# stm32.net
KiCad netlist of a schematic drawn in Altium Designer
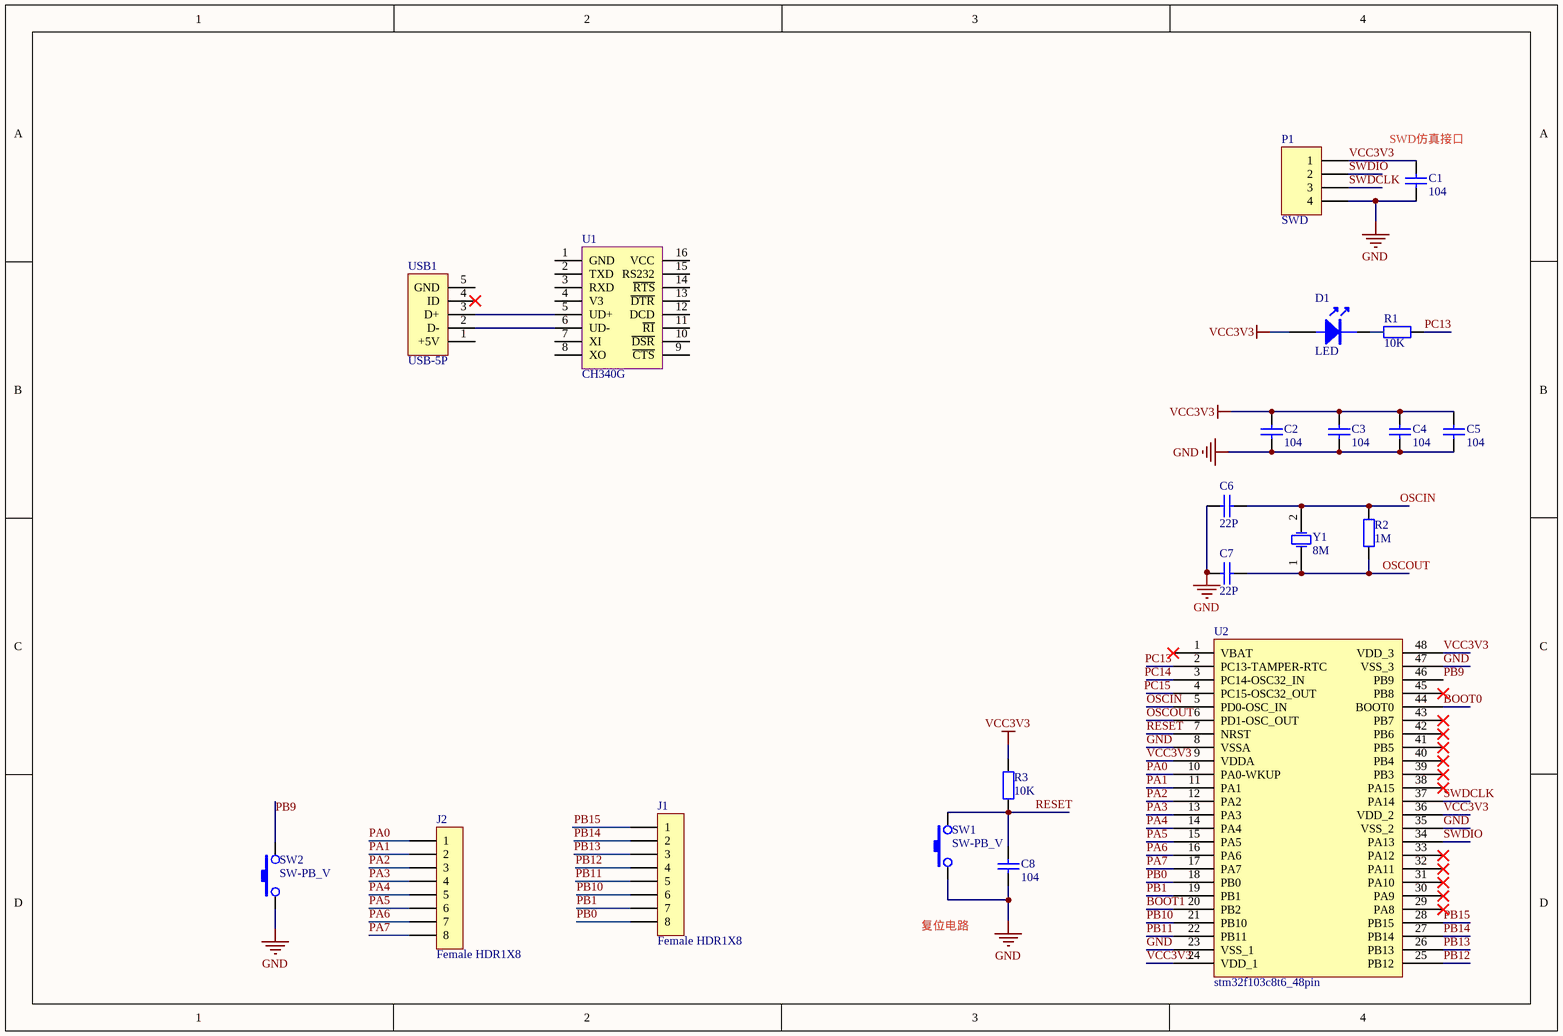
[diagram p0: stm32最小系统.SchDoc]

(export (version "E")
  (design (tool "Eeschema 10.0.6"))
  (components
    (comp (ref "C1")
      (value "104")
      (footprint "0805R")
      (fields (field (name "PUBLISHER") "Altium Limited"))
      (libsource (lib "stm32原理图库") (part "Cap"))
    )
    (comp (ref "C2")
      (value "104")
      (footprint "0805R")
      (fields (field (name "PUBLISHER") "Altium Limited"))
      (libsource (lib "stm32原理图库") (part "Cap"))
    )
    (comp (ref "C3")
      (value "104")
      (fields (field (name "PUBLISHER") "Altium Limited"))
      (libsource (lib "stm32原理图库") (part "Cap"))
    )
    (comp (ref "C4")
      (value "104")
      (fields (field (name "PUBLISHER") "Altium Limited"))
      (libsource (lib "stm32原理图库") (part "Cap"))
    )
    (comp (ref "C5")
      (value "104")
      (fields (field (name "PUBLISHER") "Altium Limited"))
      (libsource (lib "stm32原理图库") (part "Cap"))
    )
    (comp (ref "C6")
      (value "22P")
      (description "Capacitor")
      (fields (field (name "PUBLISHER") "Altium Limited"))
      (libsource (lib "STM32F103C8T6") (part "Cap"))
    )
    (comp (ref "C7")
      (value "22P")
      (description "Capacitor")
      (fields (field (name "PUBLISHER") "Altium Limited"))
      (libsource (lib "STM32F103C8T6") (part "Cap"))
    )
    (comp (ref "C8")
      (value "104")
      (footprint "0805C")
      (fields (field (name "PUBLISHER") "Altium Limited"))
      (libsource (lib "stm32原理图库") (part "Cap"))
    )
    (comp (ref "D1") (value "LED") (footprint "LED 0805G") (libsource (lib "stm32原理图库") (part "LED")))
    (comp (ref "J1")
      (value "Female HDR1X8")
      (footprint "Fe-HDR1X8/2.54-S")
      (libsource (lib "排母") (part "Female HDR1X8"))
    )
    (comp (ref "J2")
      (value "Female HDR1X8")
      (footprint "Fe-HDR1X8/2.54-S")
      (libsource (lib "排母") (part "Female HDR1X8"))
    )
    (comp (ref "P1")
      (value "SWD")
      (footprint "HDR-1X4_H")
      (description "Header, 4-Pin")
      (fields (field (name "PUBLISHER") "Altium Limited"))
      (libsource (lib "stm32原理图库") (part "Header 4"))
    )
    (comp (ref "R1")
      (value "10K")
      (footprint "C0805")
      (fields (field (name "PUBLISHER") "Altium Limited"))
      (libsource (lib "stm32原理图库") (part "Res2"))
    )
    (comp (ref "R2")
      (value "1M")
      (footprint "C0805")
      (description "Resistor")
      (fields (field (name "PUBLISHER") "Altium Limited"))
      (libsource (lib "STM32F103C8T6") (part "Res2"))
    )
    (comp (ref "R3")
      (value "10K")
      (footprint "C0805")
      (fields (field (name "PUBLISHER") "Altium Limited"))
      (libsource (lib "") (part "Res2_1"))
    )
    (comp (ref "SW1")
      (value "SW-PB_V")
      (footprint "TSW SMD-3*6*2.5")
      (libsource (lib "stm32原理图库") (part "SW-PB_V"))
    )
    (comp (ref "SW2")
      (value "SW-PB_V")
      (footprint "TSW SMD-3*6*2.5")
      (libsource (lib "stm32原理图库") (part "SW-PB_V"))
    )
    (comp (ref "U1") (value "CH340G") (libsource (lib "通讯系列IC") (part "CH340G")))
    (comp (ref "U2")
      (value "stm32f103c8t6_48pin")
      (footprint "TQFP48 7x7_L")
      (libsource (lib "STM32_Schlib") (part "stm32f103c8t6_48pin"))
    )
    (comp (ref "USB1")
      (value "USB-5P")
      (footprint "USB-MICRO_E")
      (description "微型USB母座")
      (fields (field (name "版权归属") "源创客"))
      (libsource (lib "4.1   - 接口类") (part "USB-5P"))
    )
    (comp (ref "Y1")
      (value "8M")
      (footprint "XTAL-49S DIP")
      (description "Crystal Oscillator")
      (fields (field (name "PUBLISHER") "Altium Limited"))
      (libsource (lib "STM32F103C8T6") (part "XTAL"))
    )
  )
  (nets
    (net (code "1") (name "/BOOT0") (class "Default")
      (node (ref "U2") (pin "44") (pinfunction "BOOT0_44") (pintype "passive"))
    )
    (net (code "2") (name "/BOOT1") (class "Default")
      (node (ref "U2") (pin "20") (pinfunction "PB2_20") (pintype "passive"))
    )
    (net (code "3") (name "/OSCIN") (class "Default")
      (node (ref "C6") (pin "1") (pinfunction "1_1") (pintype "passive"))
      (node (ref "R2") (pin "2") (pinfunction "2_2") (pintype "passive"))
      (node (ref "U2") (pin "5") (pinfunction "PD0-OSC_IN_5") (pintype "passive"))
      (node (ref "Y1") (pin "2") (pinfunction "OSC2_2") (pintype "passive"))
    )
    (net (code "4") (name "/OSCOUT") (class "Default")
      (node (ref "C7") (pin "1") (pinfunction "1_1") (pintype "passive"))
      (node (ref "R2") (pin "1") (pinfunction "1_1") (pintype "passive"))
      (node (ref "U2") (pin "6") (pinfunction "PD1-OSC_OUT_6") (pintype "passive"))
      (node (ref "Y1") (pin "1") (pinfunction "OSC1_1") (pintype "passive"))
    )
    (net (code "5") (name "/PA0") (class "Default")
      (node (ref "J2") (pin "1") (pinfunction "1_1") (pintype "passive"))
      (node (ref "U2") (pin "10") (pinfunction "PA0-WKUP_10") (pintype "passive"))
    )
    (net (code "6") (name "/PA1") (class "Default")
      (node (ref "J2") (pin "2") (pinfunction "2_2") (pintype "passive"))
      (node (ref "U2") (pin "11") (pinfunction "PA1_11") (pintype "passive"))
    )
    (net (code "7") (name "/PA2") (class "Default")
      (node (ref "J2") (pin "3") (pinfunction "3_3") (pintype "passive"))
      (node (ref "U2") (pin "12") (pinfunction "PA2_12") (pintype "passive"))
    )
    (net (code "8") (name "/PA3") (class "Default")
      (node (ref "J2") (pin "4") (pinfunction "4_4") (pintype "passive"))
      (node (ref "U2") (pin "13") (pinfunction "PA3_13") (pintype "passive"))
    )
    (net (code "9") (name "/PA4") (class "Default")
      (node (ref "J2") (pin "5") (pinfunction "5_5") (pintype "passive"))
      (node (ref "U2") (pin "14") (pinfunction "PA4_14") (pintype "passive"))
    )
    (net (code "10") (name "/PA5") (class "Default")
      (node (ref "J2") (pin "6") (pinfunction "6_6") (pintype "passive"))
      (node (ref "U2") (pin "15") (pinfunction "PA5_15") (pintype "passive"))
    )
    (net (code "11") (name "/PA6") (class "Default")
      (node (ref "J2") (pin "7") (pinfunction "7_7") (pintype "passive"))
      (node (ref "U2") (pin "16") (pinfunction "PA6_16") (pintype "passive"))
    )
    (net (code "12") (name "/PA7") (class "Default")
      (node (ref "J2") (pin "8") (pinfunction "8_8") (pintype "passive"))
      (node (ref "U2") (pin "17") (pinfunction "PA7_17") (pintype "passive"))
    )
    (net (code "13") (name "/PB0") (class "Default")
      (node (ref "J1") (pin "8") (pinfunction "8_8") (pintype "passive"))
      (node (ref "U2") (pin "18") (pinfunction "PB0_18") (pintype "passive"))
    )
    (net (code "14") (name "/PB1") (class "Default")
      (node (ref "J1") (pin "7") (pinfunction "7_7") (pintype "passive"))
      (node (ref "U2") (pin "19") (pinfunction "PB1_19") (pintype "passive"))
    )
    (net (code "15") (name "/PB9") (class "Default")
      (node (ref "SW2") (pin "2") (pinfunction "2_2") (pintype "passive"))
      (node (ref "U2") (pin "46") (pinfunction "PB9_46") (pintype "passive"))
    )
    (net (code "16") (name "/PB10") (class "Default")
      (node (ref "J1") (pin "6") (pinfunction "6_6") (pintype "passive"))
      (node (ref "U2") (pin "21") (pinfunction "PB10_21") (pintype "passive"))
    )
    (net (code "17") (name "/PB11") (class "Default")
      (node (ref "J1") (pin "5") (pinfunction "5_5") (pintype "passive"))
      (node (ref "U2") (pin "22") (pinfunction "PB11_22") (pintype "passive"))
    )
    (net (code "18") (name "/PB12") (class "Default")
      (node (ref "J1") (pin "4") (pinfunction "4_4") (pintype "passive"))
      (node (ref "U2") (pin "25") (pinfunction "PB12_25") (pintype "passive"))
    )
    (net (code "19") (name "/PB13") (class "Default")
      (node (ref "J1") (pin "3") (pinfunction "3_3") (pintype "passive"))
      (node (ref "U2") (pin "26") (pinfunction "PB13_26") (pintype "passive"))
    )
    (net (code "20") (name "/PB14") (class "Default")
      (node (ref "J1") (pin "2") (pinfunction "2_2") (pintype "passive"))
      (node (ref "U2") (pin "27") (pinfunction "PB14_27") (pintype "passive"))
    )
    (net (code "21") (name "/PB15") (class "Default")
      (node (ref "J1") (pin "1") (pinfunction "1_1") (pintype "passive"))
      (node (ref "U2") (pin "28") (pinfunction "PB15_28") (pintype "passive"))
    )
    (net (code "22") (name "/PC13") (class "Default")
      (node (ref "R1") (pin "2") (pinfunction "2_2") (pintype "passive"))
      (node (ref "U2") (pin "2") (pinfunction "PC13-TAMPER-RTC_2") (pintype "passive"))
    )
    (net (code "23") (name "/PC14") (class "Default")
      (node (ref "U2") (pin "3") (pinfunction "PC14-OSC32_IN_3") (pintype "passive"))
    )
    (net (code "24") (name "/PC15") (class "Default")
      (node (ref "U2") (pin "4") (pinfunction "PC15-OSC32_OUT_4") (pintype "passive"))
    )
    (net (code "25") (name "/RESET") (class "Default")
      (node (ref "C8") (pin "2") (pinfunction "2_2") (pintype "passive"))
      (node (ref "R3") (pin "1") (pinfunction "1_1") (pintype "passive"))
      (node (ref "SW1") (pin "2") (pinfunction "2_2") (pintype "passive"))
      (node (ref "U2") (pin "7") (pinfunction "NRST_7") (pintype "passive"))
    )
    (net (code "26") (name "/SWDCLK") (class "Default")
      (node (ref "P1") (pin "3") (pinfunction "3_3") (pintype "passive"))
      (node (ref "U2") (pin "37") (pinfunction "PA14_37") (pintype "passive"))
    )
    (net (code "27") (name "/SWDIO") (class "Default")
      (node (ref "P1") (pin "2") (pinfunction "2_2") (pintype "passive"))
      (node (ref "U2") (pin "34") (pinfunction "PA13_34") (pintype "passive"))
    )
    (net (code "28") (name "GND") (class "Default")
      (node (ref "C1") (pin "1") (pinfunction "1_1") (pintype "passive"))
      (node (ref "C2") (pin "1") (pinfunction "1_1") (pintype "passive"))
      (node (ref "C3") (pin "1") (pinfunction "1_1") (pintype "passive"))
      (node (ref "C4") (pin "1") (pinfunction "1_1") (pintype "passive"))
      (node (ref "C5") (pin "1") (pinfunction "1_1") (pintype "passive"))
      (node (ref "C6") (pin "2") (pinfunction "2_2") (pintype "passive"))
      (node (ref "C7") (pin "2") (pinfunction "2_2") (pintype "passive"))
      (node (ref "C8") (pin "1") (pinfunction "1_1") (pintype "passive"))
      (node (ref "P1") (pin "4") (pinfunction "4_4") (pintype "passive"))
      (node (ref "SW1") (pin "1") (pinfunction "1_1") (pintype "passive"))
      (node (ref "SW2") (pin "1") (pinfunction "1_1") (pintype "passive"))
      (node (ref "U2") (pin "23") (pinfunction "VSS_1_23") (pintype "passive"))
      (node (ref "U2") (pin "35") (pinfunction "VSS_2_35") (pintype "passive"))
      (node (ref "U2") (pin "47") (pinfunction "VSS_3_47") (pintype "passive"))
      (node (ref "U2") (pin "8") (pinfunction "VSSA_8") (pintype "passive"))
    )
    (net (code "29") (name "Net-(D1-Pad2)") (class "Default")
      (node (ref "D1") (pin "2") (pinfunction "2_2") (pintype "passive"))
      (node (ref "R1") (pin "1") (pinfunction "1_1") (pintype "passive"))
    )
    (net (code "30") (name "Net-(U1-UD+)") (class "Default")
      (node (ref "U1") (pin "5") (pinfunction "UD+_5") (pintype "passive"))
      (node (ref "USB1") (pin "3") (pinfunction "D+_3") (pintype "passive"))
    )
    (net (code "31") (name "Net-(U1-UD-)") (class "Default")
      (node (ref "U1") (pin "6") (pinfunction "UD-_6") (pintype "passive"))
      (node (ref "USB1") (pin "2") (pinfunction "D-_2") (pintype "passive"))
    )
    (net (code "32") (name "VCC3V3") (class "Default")
      (node (ref "C1") (pin "2") (pinfunction "2_2") (pintype "passive"))
      (node (ref "C2") (pin "2") (pinfunction "2_2") (pintype "passive"))
      (node (ref "C3") (pin "2") (pinfunction "2_2") (pintype "passive"))
      (node (ref "C4") (pin "2") (pinfunction "2_2") (pintype "passive"))
      (node (ref "C5") (pin "2") (pinfunction "2_2") (pintype "passive"))
      (node (ref "D1") (pin "1") (pinfunction "1_1") (pintype "passive"))
      (node (ref "P1") (pin "1") (pinfunction "1_1") (pintype "passive"))
      (node (ref "R3") (pin "2") (pinfunction "2_2") (pintype "passive"))
      (node (ref "U2") (pin "24") (pinfunction "VDD_1_24") (pintype "passive"))
      (node (ref "U2") (pin "36") (pinfunction "VDD_2_36") (pintype "passive"))
      (node (ref "U2") (pin "48") (pinfunction "VDD_3_48") (pintype "passive"))
      (node (ref "U2") (pin "9") (pinfunction "VDDA_9") (pintype "passive"))
    )
    (net (code "33") (name "unconnected-(U1-DCD-Pad12)") (class "Default")
      (node (ref "U1") (pin "12") (pinfunction "DCD_12") (pintype "passive"))
    )
    (net (code "34") (name "unconnected-(U1-GND-Pad1)") (class "Default")
      (node (ref "U1") (pin "1") (pinfunction "GND_1") (pintype "passive"))
    )
    (net (code "35") (name "unconnected-(U1-RS232-Pad15)") (class "Default")
      (node (ref "U1") (pin "15") (pinfunction "RS232_15") (pintype "passive"))
    )
    (net (code "36") (name "unconnected-(U1-RXD-Pad3)") (class "Default")
      (node (ref "U1") (pin "3") (pinfunction "RXD_3") (pintype "passive"))
    )
    (net (code "37") (name "unconnected-(U1-TXD-Pad2)") (class "Default")
      (node (ref "U1") (pin "2") (pinfunction "TXD_2") (pintype "passive"))
    )
    (net (code "38") (name "unconnected-(U1-V3-Pad4)") (class "Default")
      (node (ref "U1") (pin "4") (pinfunction "V3_4") (pintype "passive"))
    )
    (net (code "39") (name "unconnected-(U1-VCC-Pad16)") (class "Default")
      (node (ref "U1") (pin "16") (pinfunction "VCC_16") (pintype "passive"))
    )
    (net (code "40") (name "unconnected-(U1-XI-Pad7)") (class "Default")
      (node (ref "U1") (pin "7") (pinfunction "XI_7") (pintype "passive"))
    )
    (net (code "41") (name "unconnected-(U1-XO-Pad8)") (class "Default")
      (node (ref "U1") (pin "8") (pinfunction "XO_8") (pintype "passive"))
    )
    (net (code "42") (name "unconnected-(U1-~{CTS}-Pad9)") (class "Default")
      (node (ref "U1") (pin "9") (pinfunction "~{CTS}_9") (pintype "passive"))
    )
    (net (code "43") (name "unconnected-(U1-~{DSR}-Pad10)") (class "Default")
      (node (ref "U1") (pin "10") (pinfunction "~{DSR}_10") (pintype "passive"))
    )
    (net (code "44") (name "unconnected-(U1-~{DTR}-Pad13)") (class "Default")
      (node (ref "U1") (pin "13") (pinfunction "~{DTR}_13") (pintype "passive"))
    )
    (net (code "45") (name "unconnected-(U1-~{RI}-Pad11)") (class "Default")
      (node (ref "U1") (pin "11") (pinfunction "~{RI}_11") (pintype "passive"))
    )
    (net (code "46") (name "unconnected-(U1-~{RTS}-Pad14)") (class "Default")
      (node (ref "U1") (pin "14") (pinfunction "~{RTS}_14") (pintype "passive"))
    )
    (net (code "47") (name "unconnected-(U2-PA8-Pad29)") (class "Default")
      (node (ref "U2") (pin "29") (pinfunction "PA8_29") (pintype "passive+no_connect"))
    )
    (net (code "48") (name "unconnected-(U2-PA9-Pad30)") (class "Default")
      (node (ref "U2") (pin "30") (pinfunction "PA9_30") (pintype "passive+no_connect"))
    )
    (net (code "49") (name "unconnected-(U2-PA10-Pad31)") (class "Default")
      (node (ref "U2") (pin "31") (pinfunction "PA10_31") (pintype "passive+no_connect"))
    )
    (net (code "50") (name "unconnected-(U2-PA11-Pad32)") (class "Default")
      (node (ref "U2") (pin "32") (pinfunction "PA11_32") (pintype "passive+no_connect"))
    )
    (net (code "51") (name "unconnected-(U2-PA12-Pad33)") (class "Default")
      (node (ref "U2") (pin "33") (pinfunction "PA12_33") (pintype "passive+no_connect"))
    )
    (net (code "52") (name "unconnected-(U2-PA15-Pad38)") (class "Default")
      (node (ref "U2") (pin "38") (pinfunction "PA15_38") (pintype "passive+no_connect"))
    )
    (net (code "53") (name "unconnected-(U2-PB3-Pad39)") (class "Default")
      (node (ref "U2") (pin "39") (pinfunction "PB3_39") (pintype "passive+no_connect"))
    )
    (net (code "54") (name "unconnected-(U2-PB4-Pad40)") (class "Default")
      (node (ref "U2") (pin "40") (pinfunction "PB4_40") (pintype "passive+no_connect"))
    )
    (net (code "55") (name "unconnected-(U2-PB5-Pad41)") (class "Default")
      (node (ref "U2") (pin "41") (pinfunction "PB5_41") (pintype "passive+no_connect"))
    )
    (net (code "56") (name "unconnected-(U2-PB6-Pad42)") (class "Default")
      (node (ref "U2") (pin "42") (pinfunction "PB6_42") (pintype "passive+no_connect"))
    )
    (net (code "57") (name "unconnected-(U2-PB7-Pad43)") (class "Default")
      (node (ref "U2") (pin "43") (pinfunction "PB7_43") (pintype "passive+no_connect"))
    )
    (net (code "58") (name "unconnected-(U2-PB8-Pad45)") (class "Default")
      (node (ref "U2") (pin "45") (pinfunction "PB8_45") (pintype "passive+no_connect"))
    )
    (net (code "59") (name "unconnected-(U2-VBAT-Pad1)") (class "Default")
      (node (ref "U2") (pin "1") (pinfunction "VBAT_1") (pintype "passive+no_connect"))
    )
    (net (code "60") (name "unconnected-(USB1-+5V-Pad1)") (class "Default")
      (node (ref "USB1") (pin "1") (pinfunction "+5V_1") (pintype "passive"))
    )
    (net (code "61") (name "unconnected-(USB1-GND-Pad5)") (class "Default")
      (node (ref "USB1") (pin "5") (pinfunction "GND_5") (pintype "passive"))
    )
    (net (code "62") (name "unconnected-(USB1-ID-Pad4)") (class "Default")
      (node (ref "USB1") (pin "4") (pinfunction "ID_4") (pintype "passive+no_connect"))
    )
  )
)
